# stantion.net
KiCad netlist of a schematic drawn in EAGLE
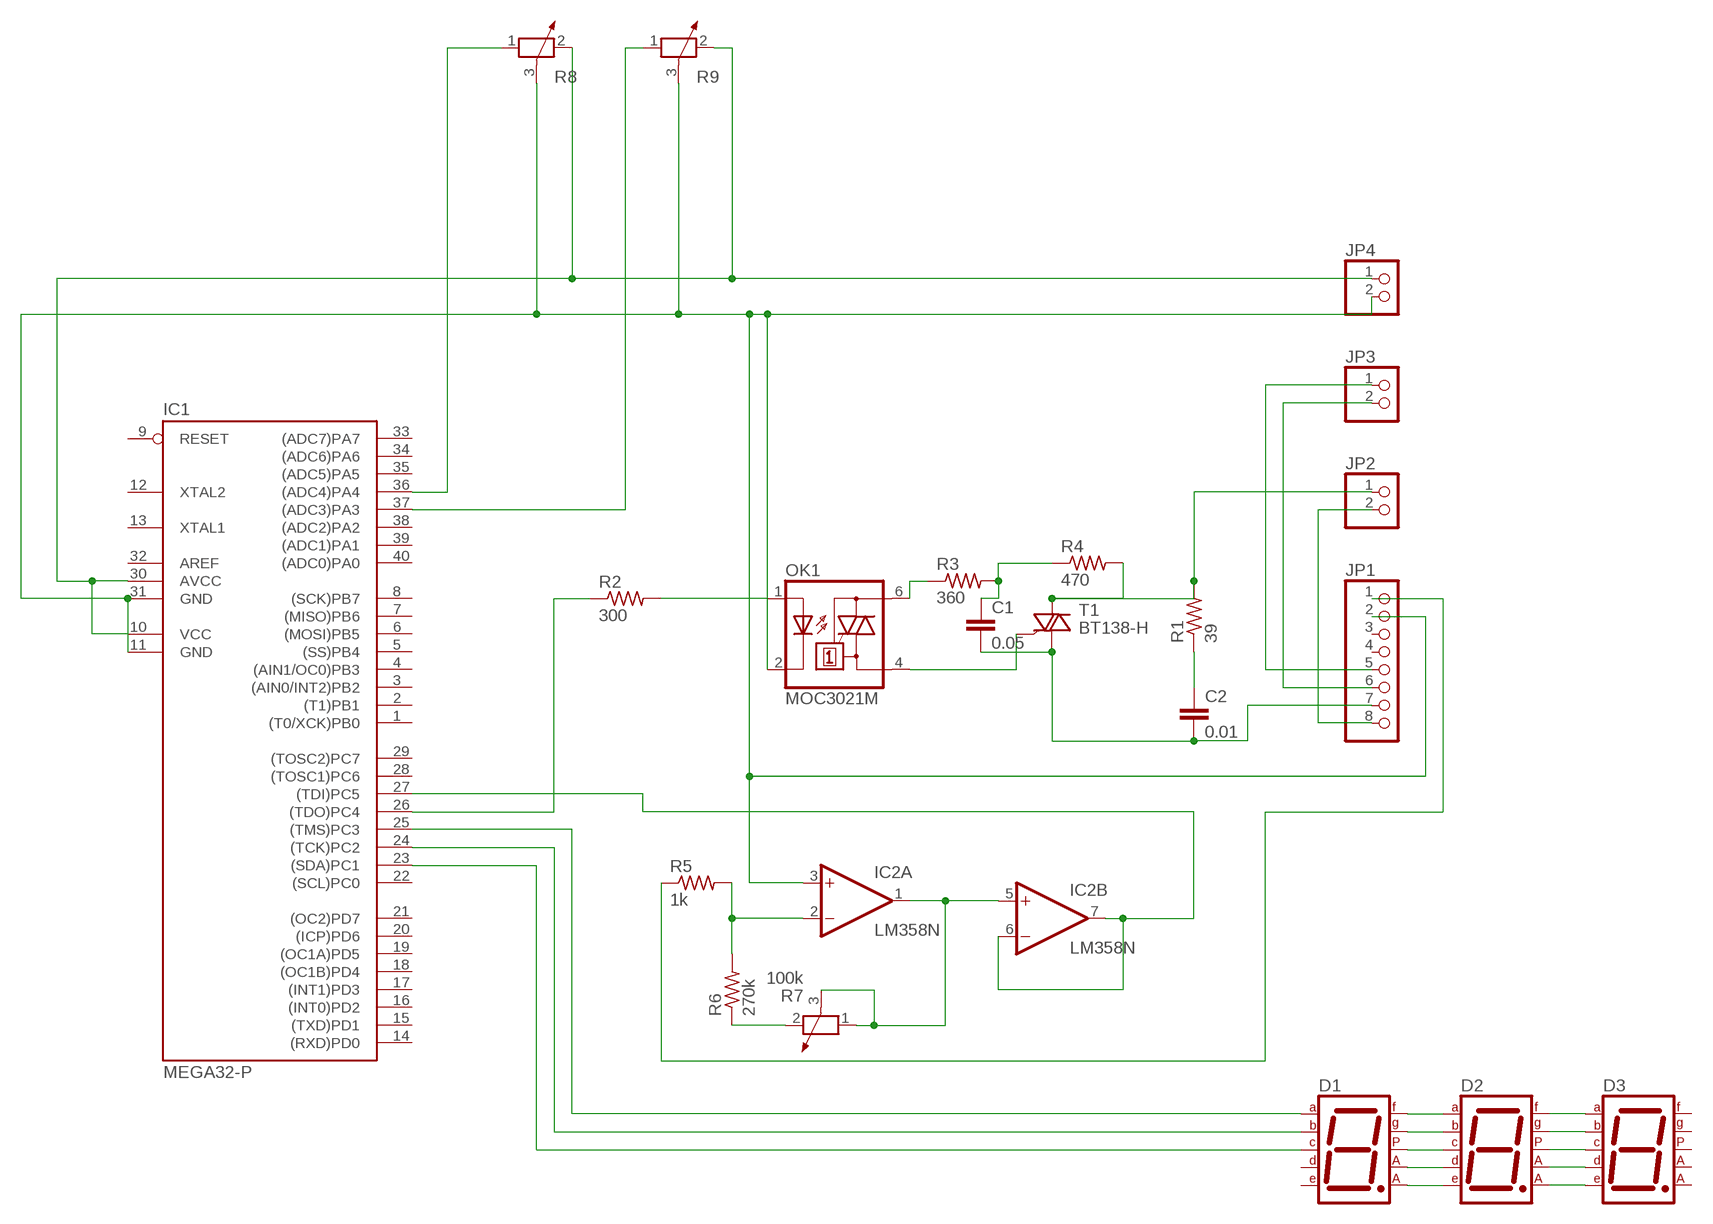
[diagram p0: schematic, sheet 1]

(export (version "E")
  (design (tool "Eeschema 10.0.6"))
  (components
    (comp (ref "C1")
      (value "0.05")
      (footprint "eagle-import:C075-032X103")
      (libsource (lib "eagle-import") (part "C-EU075-032X103"))
    )
    (comp (ref "C2")
      (value "0.01")
      (footprint "eagle-import:C075-032X103")
      (libsource (lib "eagle-import") (part "C-EU075-032X103"))
    )
    (comp (ref "D1")
      (value "7SEG-CA")
      (footprint "eagle-import:7SEG-13")
      (libsource (lib "eagle-import") (part "7SEG-CA"))
    )
    (comp (ref "D2")
      (value "7SEG-CA")
      (footprint "eagle-import:7SEG-13")
      (libsource (lib "eagle-import") (part "7SEG-CA"))
    )
    (comp (ref "D3")
      (value "7SEG-CA")
      (footprint "eagle-import:7SEG-13")
      (libsource (lib "eagle-import") (part "7SEG-CA"))
    )
    (comp (ref "IC1")
      (value "MEGA32-P")
      (footprint "eagle-import:DIL40")
      (fields (field (name "MPN") "ATMEGA32-16PU"))
      (libsource (lib "eagle-import") (part "MEGA32-P"))
    )
    (comp (ref "IC2")
      (value "LM358N")
      (footprint "eagle-import:DIL08")
      (libsource (lib "eagle-import") (part "LM358N"))
    )
    (comp (ref "JP1")
      (value "PINHD-1X8")
      (footprint "eagle-import:1X08")
      (libsource (lib "eagle-import") (part "PINHD-1X8"))
    )
    (comp (ref "JP2")
      (value "PINHD-1X2")
      (footprint "eagle-import:1X02")
      (libsource (lib "eagle-import") (part "PINHD-1X2"))
    )
    (comp (ref "JP3")
      (value "PINHD-1X2")
      (footprint "eagle-import:1X02")
      (libsource (lib "eagle-import") (part "PINHD-1X2"))
    )
    (comp (ref "JP4")
      (value "PINHD-1X2")
      (footprint "eagle-import:1X02")
      (libsource (lib "eagle-import") (part "PINHD-1X2"))
    )
    (comp (ref "OK1")
      (value "MOC3021M")
      (footprint "eagle-import:DIL06")
      (fields (field (name "MF") "FAIRCHILD SEMICONDUCTOR") (field (name "MPN") "MOC3021-M"))
      (libsource (lib "eagle-import") (part "MOC30M21"))
    )
    (comp (ref "R1")
      (value "39")
      (footprint "eagle-import:V234_12")
      (libsource (lib "eagle-import") (part "R-US_V234/12"))
    )
    (comp (ref "R2")
      (value "300")
      (footprint "eagle-import:V234_12")
      (libsource (lib "eagle-import") (part "R-US_V234/12"))
    )
    (comp (ref "R3")
      (value "360")
      (footprint "eagle-import:V234_12")
      (libsource (lib "eagle-import") (part "R-US_V234/12"))
    )
    (comp (ref "R4")
      (value "470")
      (footprint "eagle-import:V234_12")
      (libsource (lib "eagle-import") (part "R-US_V234/12"))
    )
    (comp (ref "R5")
      (value "1k")
      (footprint "eagle-import:V234_12")
      (libsource (lib "eagle-import") (part "R-US_V234/12"))
    )
    (comp (ref "R6")
      (value "270k")
      (footprint "eagle-import:V234_12")
      (libsource (lib "eagle-import") (part "R-US_V234/12"))
    )
    (comp (ref "R7")
      (value "100k")
      (footprint "eagle-import:PT-SPIN")
      (libsource (lib "eagle-import") (part "POTENTIOMETER_PT_SPIN"))
    )
    (comp (ref "R8")
      (value "POTENTIOMETER_PT-10")
      (footprint "eagle-import:PT-10")
      (libsource (lib "eagle-import") (part "POTENTIOMETER_PT-10"))
    )
    (comp (ref "R9")
      (value "POTENTIOMETER_PT-10")
      (footprint "eagle-import:PT-10")
      (libsource (lib "eagle-import") (part "POTENTIOMETER_PT-10"))
    )
    (comp (ref "T1")
      (value "BT138-H")
      (footprint "eagle-import:TO220BH")
      (libsource (lib "eagle-import") (part "BT138-H"))
    )
  )
  (nets
    (net (code "1") (name "Net-(C1-Pad1)") (class "Default")
      (node (ref "C1") (pin "1") (pinfunction "1_1") (pintype "passive"))
      (node (ref "R3") (pin "2") (pinfunction "2_2") (pintype "passive"))
      (node (ref "R4") (pin "1") (pinfunction "1_1") (pintype "passive"))
    )
    (net (code "2") (name "Net-(C2-Pad1)") (class "Default")
      (node (ref "C2") (pin "1") (pinfunction "1_1") (pintype "passive"))
      (node (ref "R1") (pin "1") (pinfunction "1_1") (pintype "passive"))
    )
    (net (code "3") (name "Net-(D1-A)") (class "Default")
      (node (ref "D1") (pin "7") (pinfunction "A_7") (pintype "passive"))
      (node (ref "IC1") (pin "25") (pinfunction "(TMS)PC3_25") (pintype "bidirectional"))
    )
    (net (code "4") (name "Net-(D1-B)") (class "Default")
      (node (ref "D1") (pin "6") (pinfunction "B_6") (pintype "passive"))
      (node (ref "IC1") (pin "24") (pinfunction "(TCK)PC2_24") (pintype "bidirectional"))
    )
    (net (code "5") (name "Net-(D1-C)") (class "Default")
      (node (ref "D1") (pin "4") (pinfunction "C_4") (pintype "passive"))
      (node (ref "IC1") (pin "23") (pinfunction "(SDA)PC1_23") (pintype "bidirectional"))
    )
    (net (code "6") (name "Net-(D1-CA1)") (class "Default")
      (node (ref "D1") (pin "3") (pinfunction "CA1_3") (pintype "passive"))
      (node (ref "D2") (pin "2") (pinfunction "D_2") (pintype "passive"))
    )
    (net (code "7") (name "Net-(D1-CA2)") (class "Default")
      (node (ref "D1") (pin "8") (pinfunction "CA2_8") (pintype "passive"))
      (node (ref "D2") (pin "1") (pinfunction "E_1") (pintype "passive"))
    )
    (net (code "8") (name "Net-(D1-DP)") (class "Default")
      (node (ref "D1") (pin "5") (pinfunction "DP_5") (pintype "passive"))
      (node (ref "D2") (pin "4") (pinfunction "C_4") (pintype "passive"))
    )
    (net (code "9") (name "Net-(D1-F)") (class "Default")
      (node (ref "D1") (pin "9") (pinfunction "F_9") (pintype "passive"))
      (node (ref "D2") (pin "7") (pinfunction "A_7") (pintype "passive"))
    )
    (net (code "10") (name "Net-(D1-G)") (class "Default")
      (node (ref "D1") (pin "10") (pinfunction "G_10") (pintype "passive"))
      (node (ref "D2") (pin "6") (pinfunction "B_6") (pintype "passive"))
    )
    (net (code "11") (name "Net-(D2-CA1)") (class "Default")
      (node (ref "D2") (pin "3") (pinfunction "CA1_3") (pintype "passive"))
      (node (ref "D3") (pin "2") (pinfunction "D_2") (pintype "passive"))
    )
    (net (code "12") (name "Net-(D2-CA2)") (class "Default")
      (node (ref "D2") (pin "8") (pinfunction "CA2_8") (pintype "passive"))
      (node (ref "D3") (pin "1") (pinfunction "E_1") (pintype "passive"))
    )
    (net (code "13") (name "Net-(D2-DP)") (class "Default")
      (node (ref "D2") (pin "5") (pinfunction "DP_5") (pintype "passive"))
      (node (ref "D3") (pin "4") (pinfunction "C_4") (pintype "passive"))
    )
    (net (code "14") (name "Net-(D2-F)") (class "Default")
      (node (ref "D2") (pin "9") (pinfunction "F_9") (pintype "passive"))
      (node (ref "D3") (pin "7") (pinfunction "A_7") (pintype "passive"))
    )
    (net (code "15") (name "Net-(D2-G)") (class "Default")
      (node (ref "D2") (pin "10") (pinfunction "G_10") (pintype "passive"))
      (node (ref "D3") (pin "6") (pinfunction "B_6") (pintype "passive"))
    )
    (net (code "16") (name "Net-(IC1-(ADC3)PA3)") (class "Default")
      (node (ref "IC1") (pin "37") (pinfunction "(ADC3)PA3_37") (pintype "bidirectional"))
      (node (ref "R9") (pin "1") (pinfunction "1_1") (pintype "passive"))
    )
    (net (code "17") (name "Net-(IC1-(ADC4)PA4)") (class "Default")
      (node (ref "IC1") (pin "36") (pinfunction "(ADC4)PA4_36") (pintype "bidirectional"))
      (node (ref "R8") (pin "1") (pinfunction "1_1") (pintype "passive"))
    )
    (net (code "18") (name "Net-(IC1-(TDI)PC5)") (class "Default")
      (node (ref "IC1") (pin "27") (pinfunction "(TDI)PC5_27") (pintype "bidirectional"))
      (node (ref "IC2") (pin "6") (pinfunction "-IN_6") (pintype "input"))
      (node (ref "IC2") (pin "7") (pinfunction "OUT_7") (pintype "output"))
    )
    (net (code "19") (name "Net-(IC1-(TDO)PC4)") (class "Default")
      (node (ref "IC1") (pin "26") (pinfunction "(TDO)PC4_26") (pintype "bidirectional"))
      (node (ref "R2") (pin "1") (pinfunction "1_1") (pintype "passive"))
    )
    (net (code "20") (name "Net-(IC1-AVCC)") (class "Default")
      (node (ref "IC1") (pin "10") (pinfunction "VCC_10") (pintype "power_in"))
      (node (ref "IC1") (pin "30") (pinfunction "AVCC_30") (pintype "power_in"))
      (node (ref "JP4") (pin "1") (pinfunction "1_1") (pintype "passive"))
      (node (ref "R8") (pin "2") (pinfunction "2_2") (pintype "passive"))
      (node (ref "R9") (pin "2") (pinfunction "2_2") (pintype "passive"))
    )
    (net (code "21") (name "Net-(IC2A-+IN)") (class "Default")
      (node (ref "IC1") (pin "11") (pinfunction "GND_11") (pintype "power_in"))
      (node (ref "IC1") (pin "31") (pinfunction "GND_31") (pintype "power_in"))
      (node (ref "IC2") (pin "3") (pinfunction "+IN_3") (pintype "input"))
      (node (ref "JP1") (pin "2") (pinfunction "2_2") (pintype "passive"))
      (node (ref "JP4") (pin "2") (pinfunction "2_2") (pintype "passive"))
      (node (ref "OK1") (pin "2") (pinfunction "C_2") (pintype "passive"))
      (node (ref "R8") (pin "3") (pinfunction "3_3") (pintype "passive"))
      (node (ref "R9") (pin "3") (pinfunction "3_3") (pintype "passive"))
    )
    (net (code "22") (name "Net-(IC2A--IN)") (class "Default")
      (node (ref "IC2") (pin "2") (pinfunction "-IN_2") (pintype "input"))
      (node (ref "R5") (pin "2") (pinfunction "2_2") (pintype "passive"))
      (node (ref "R6") (pin "2") (pinfunction "2_2") (pintype "passive"))
    )
    (net (code "23") (name "Net-(IC2A-OUT)") (class "Default")
      (node (ref "IC2") (pin "1") (pinfunction "OUT_1") (pintype "output"))
      (node (ref "IC2") (pin "5") (pinfunction "+IN_5") (pintype "input"))
      (node (ref "R7") (pin "1") (pinfunction "1_1") (pintype "passive"))
      (node (ref "R7") (pin "3") (pinfunction "3_3") (pintype "passive"))
    )
    (net (code "24") (name "Net-(JP1-Pad1)") (class "Default")
      (node (ref "JP1") (pin "1") (pinfunction "1_1") (pintype "passive"))
      (node (ref "R5") (pin "1") (pinfunction "1_1") (pintype "passive"))
    )
    (net (code "25") (name "Net-(JP1-Pad5)") (class "Default")
      (node (ref "JP1") (pin "5") (pinfunction "5_5") (pintype "passive"))
      (node (ref "JP3") (pin "1") (pinfunction "1_1") (pintype "passive"))
    )
    (net (code "26") (name "Net-(JP1-Pad6)") (class "Default")
      (node (ref "JP1") (pin "6") (pinfunction "6_6") (pintype "passive"))
      (node (ref "JP3") (pin "2") (pinfunction "2_2") (pintype "passive"))
    )
    (net (code "27") (name "Net-(JP1-Pad8)") (class "Default")
      (node (ref "JP1") (pin "8") (pinfunction "8_8") (pintype "passive"))
      (node (ref "JP2") (pin "2") (pinfunction "2_2") (pintype "passive"))
    )
    (net (code "28") (name "Net-(OK1-A)") (class "Default")
      (node (ref "OK1") (pin "1") (pinfunction "A_1") (pintype "passive"))
      (node (ref "R2") (pin "2") (pinfunction "2_2") (pintype "passive"))
    )
    (net (code "29") (name "Net-(OK1-A1)") (class "Default")
      (node (ref "OK1") (pin "4") (pinfunction "A1_4") (pintype "passive"))
      (node (ref "T1") (pin "G") (pinfunction "G_G") (pintype "passive"))
    )
    (net (code "30") (name "Net-(OK1-A2)") (class "Default")
      (node (ref "OK1") (pin "6") (pinfunction "A2_6") (pintype "passive"))
      (node (ref "R3") (pin "1") (pinfunction "1_1") (pintype "passive"))
    )
    (net (code "31") (name "Net-(R6-Pad1)") (class "Default")
      (node (ref "R6") (pin "1") (pinfunction "1_1") (pintype "passive"))
      (node (ref "R7") (pin "2") (pinfunction "2_2") (pintype "passive"))
    )
    (net (code "32") (name "Net-(T1-A1)") (class "Default")
      (node (ref "C1") (pin "2") (pinfunction "2_2") (pintype "passive"))
      (node (ref "C2") (pin "2") (pinfunction "2_2") (pintype "passive"))
      (node (ref "JP1") (pin "7") (pinfunction "7_7") (pintype "passive"))
      (node (ref "T1") (pin "T1") (pinfunction "A1_T1") (pintype "passive"))
    )
    (net (code "33") (name "Net-(T1-A2)") (class "Default")
      (node (ref "JP2") (pin "1") (pinfunction "1_1") (pintype "passive"))
      (node (ref "R1") (pin "2") (pinfunction "2_2") (pintype "passive"))
      (node (ref "R4") (pin "2") (pinfunction "2_2") (pintype "passive"))
      (node (ref "T1") (pin "T2") (pinfunction "A2_T2") (pintype "passive"))
    )
    (net (code "34") (name "unconnected-(D1-D-Pad2)") (class "Default")
      (node (ref "D1") (pin "2") (pinfunction "D_2") (pintype "passive"))
    )
    (net (code "35") (name "unconnected-(D1-E-Pad1)") (class "Default")
      (node (ref "D1") (pin "1") (pinfunction "E_1") (pintype "passive"))
    )
    (net (code "36") (name "unconnected-(D3-CA1-Pad3)") (class "Default")
      (node (ref "D3") (pin "3") (pinfunction "CA1_3") (pintype "passive"))
    )
    (net (code "37") (name "unconnected-(D3-CA2-Pad8)") (class "Default")
      (node (ref "D3") (pin "8") (pinfunction "CA2_8") (pintype "passive"))
    )
    (net (code "38") (name "unconnected-(D3-DP-Pad5)") (class "Default")
      (node (ref "D3") (pin "5") (pinfunction "DP_5") (pintype "passive"))
    )
    (net (code "39") (name "unconnected-(D3-F-Pad9)") (class "Default")
      (node (ref "D3") (pin "9") (pinfunction "F_9") (pintype "passive"))
    )
    (net (code "40") (name "unconnected-(D3-G-Pad10)") (class "Default")
      (node (ref "D3") (pin "10") (pinfunction "G_10") (pintype "passive"))
    )
    (net (code "41") (name "unconnected-(IC1-(ADC0)PA0-Pad40)") (class "Default")
      (node (ref "IC1") (pin "40") (pinfunction "(ADC0)PA0_40") (pintype "bidirectional"))
    )
    (net (code "42") (name "unconnected-(IC1-(ADC1)PA1-Pad39)") (class "Default")
      (node (ref "IC1") (pin "39") (pinfunction "(ADC1)PA1_39") (pintype "bidirectional"))
    )
    (net (code "43") (name "unconnected-(IC1-(ADC2)PA2-Pad38)") (class "Default")
      (node (ref "IC1") (pin "38") (pinfunction "(ADC2)PA2_38") (pintype "bidirectional"))
    )
    (net (code "44") (name "unconnected-(IC1-(ADC5)PA5-Pad35)") (class "Default")
      (node (ref "IC1") (pin "35") (pinfunction "(ADC5)PA5_35") (pintype "bidirectional"))
    )
    (net (code "45") (name "unconnected-(IC1-(ADC6)PA6-Pad34)") (class "Default")
      (node (ref "IC1") (pin "34") (pinfunction "(ADC6)PA6_34") (pintype "bidirectional"))
    )
    (net (code "46") (name "unconnected-(IC1-(ADC7)PA7-Pad33)") (class "Default")
      (node (ref "IC1") (pin "33") (pinfunction "(ADC7)PA7_33") (pintype "bidirectional"))
    )
    (net (code "47") (name "unconnected-(IC1-(AIN0{slash}INT2)PB2-Pad3)") (class "Default")
      (node (ref "IC1") (pin "3") (pinfunction "(AIN0/INT2)PB2_3") (pintype "bidirectional"))
    )
    (net (code "48") (name "unconnected-(IC1-(AIN1{slash}OC0)PB3-Pad4)") (class "Default")
      (node (ref "IC1") (pin "4") (pinfunction "(AIN1/OC0)PB3_4") (pintype "bidirectional"))
    )
    (net (code "49") (name "unconnected-(IC1-(ICP)PD6-Pad20)") (class "Default")
      (node (ref "IC1") (pin "20") (pinfunction "(ICP)PD6_20") (pintype "bidirectional"))
    )
    (net (code "50") (name "unconnected-(IC1-(INT0)PD2-Pad16)") (class "Default")
      (node (ref "IC1") (pin "16") (pinfunction "(INT0)PD2_16") (pintype "bidirectional"))
    )
    (net (code "51") (name "unconnected-(IC1-(INT1)PD3-Pad17)") (class "Default")
      (node (ref "IC1") (pin "17") (pinfunction "(INT1)PD3_17") (pintype "bidirectional"))
    )
    (net (code "52") (name "unconnected-(IC1-(MISO)PB6-Pad7)") (class "Default")
      (node (ref "IC1") (pin "7") (pinfunction "(MISO)PB6_7") (pintype "bidirectional"))
    )
    (net (code "53") (name "unconnected-(IC1-(MOSI)PB5-Pad6)") (class "Default")
      (node (ref "IC1") (pin "6") (pinfunction "(MOSI)PB5_6") (pintype "bidirectional"))
    )
    (net (code "54") (name "unconnected-(IC1-(OC1A)PD5-Pad19)") (class "Default")
      (node (ref "IC1") (pin "19") (pinfunction "(OC1A)PD5_19") (pintype "bidirectional"))
    )
    (net (code "55") (name "unconnected-(IC1-(OC1B)PD4-Pad18)") (class "Default")
      (node (ref "IC1") (pin "18") (pinfunction "(OC1B)PD4_18") (pintype "bidirectional"))
    )
    (net (code "56") (name "unconnected-(IC1-(OC2)PD7-Pad21)") (class "Default")
      (node (ref "IC1") (pin "21") (pinfunction "(OC2)PD7_21") (pintype "bidirectional"))
    )
    (net (code "57") (name "unconnected-(IC1-(RXD)PD0-Pad14)") (class "Default")
      (node (ref "IC1") (pin "14") (pinfunction "(RXD)PD0_14") (pintype "bidirectional"))
    )
    (net (code "58") (name "unconnected-(IC1-(SCK)PB7-Pad8)") (class "Default")
      (node (ref "IC1") (pin "8") (pinfunction "(SCK)PB7_8") (pintype "bidirectional"))
    )
    (net (code "59") (name "unconnected-(IC1-(SCL)PC0-Pad22)") (class "Default")
      (node (ref "IC1") (pin "22") (pinfunction "(SCL)PC0_22") (pintype "bidirectional"))
    )
    (net (code "60") (name "unconnected-(IC1-(SS)PB4-Pad5)") (class "Default")
      (node (ref "IC1") (pin "5") (pinfunction "(SS)PB4_5") (pintype "bidirectional"))
    )
    (net (code "61") (name "unconnected-(IC1-(T0{slash}XCK)PB0-Pad1)") (class "Default")
      (node (ref "IC1") (pin "1") (pinfunction "(T0/XCK)PB0_1") (pintype "bidirectional"))
    )
    (net (code "62") (name "unconnected-(IC1-(T1)PB1-Pad2)") (class "Default")
      (node (ref "IC1") (pin "2") (pinfunction "(T1)PB1_2") (pintype "bidirectional"))
    )
    (net (code "63") (name "unconnected-(IC1-(TOSC1)PC6-Pad28)") (class "Default")
      (node (ref "IC1") (pin "28") (pinfunction "(TOSC1)PC6_28") (pintype "bidirectional"))
    )
    (net (code "64") (name "unconnected-(IC1-(TOSC2)PC7-Pad29)") (class "Default")
      (node (ref "IC1") (pin "29") (pinfunction "(TOSC2)PC7_29") (pintype "bidirectional"))
    )
    (net (code "65") (name "unconnected-(IC1-(TXD)PD1-Pad15)") (class "Default")
      (node (ref "IC1") (pin "15") (pinfunction "(TXD)PD1_15") (pintype "bidirectional"))
    )
    (net (code "66") (name "unconnected-(IC1-AREF-Pad32)") (class "Default")
      (node (ref "IC1") (pin "32") (pinfunction "AREF_32") (pintype "passive"))
    )
    (net (code "67") (name "unconnected-(IC1-RESET-Pad9)") (class "Default")
      (node (ref "IC1") (pin "9") (pinfunction "RESET_9") (pintype "input"))
    )
    (net (code "68") (name "unconnected-(IC1-XTAL1-Pad13)") (class "Default")
      (node (ref "IC1") (pin "13") (pinfunction "XTAL1_13") (pintype "bidirectional"))
    )
    (net (code "69") (name "unconnected-(IC1-XTAL2-Pad12)") (class "Default")
      (node (ref "IC1") (pin "12") (pinfunction "XTAL2_12") (pintype "bidirectional"))
    )
    (net (code "70") (name "unconnected-(JP1-Pad3)") (class "Default")
      (node (ref "JP1") (pin "3") (pinfunction "3_3") (pintype "passive"))
    )
    (net (code "71") (name "unconnected-(JP1-Pad4)") (class "Default")
      (node (ref "JP1") (pin "4") (pinfunction "4_4") (pintype "passive"))
    )
  )
)
